# SCH_linefollower_2024-05-15.net
KiCad netlist of a schematic drawn in EasyEDA
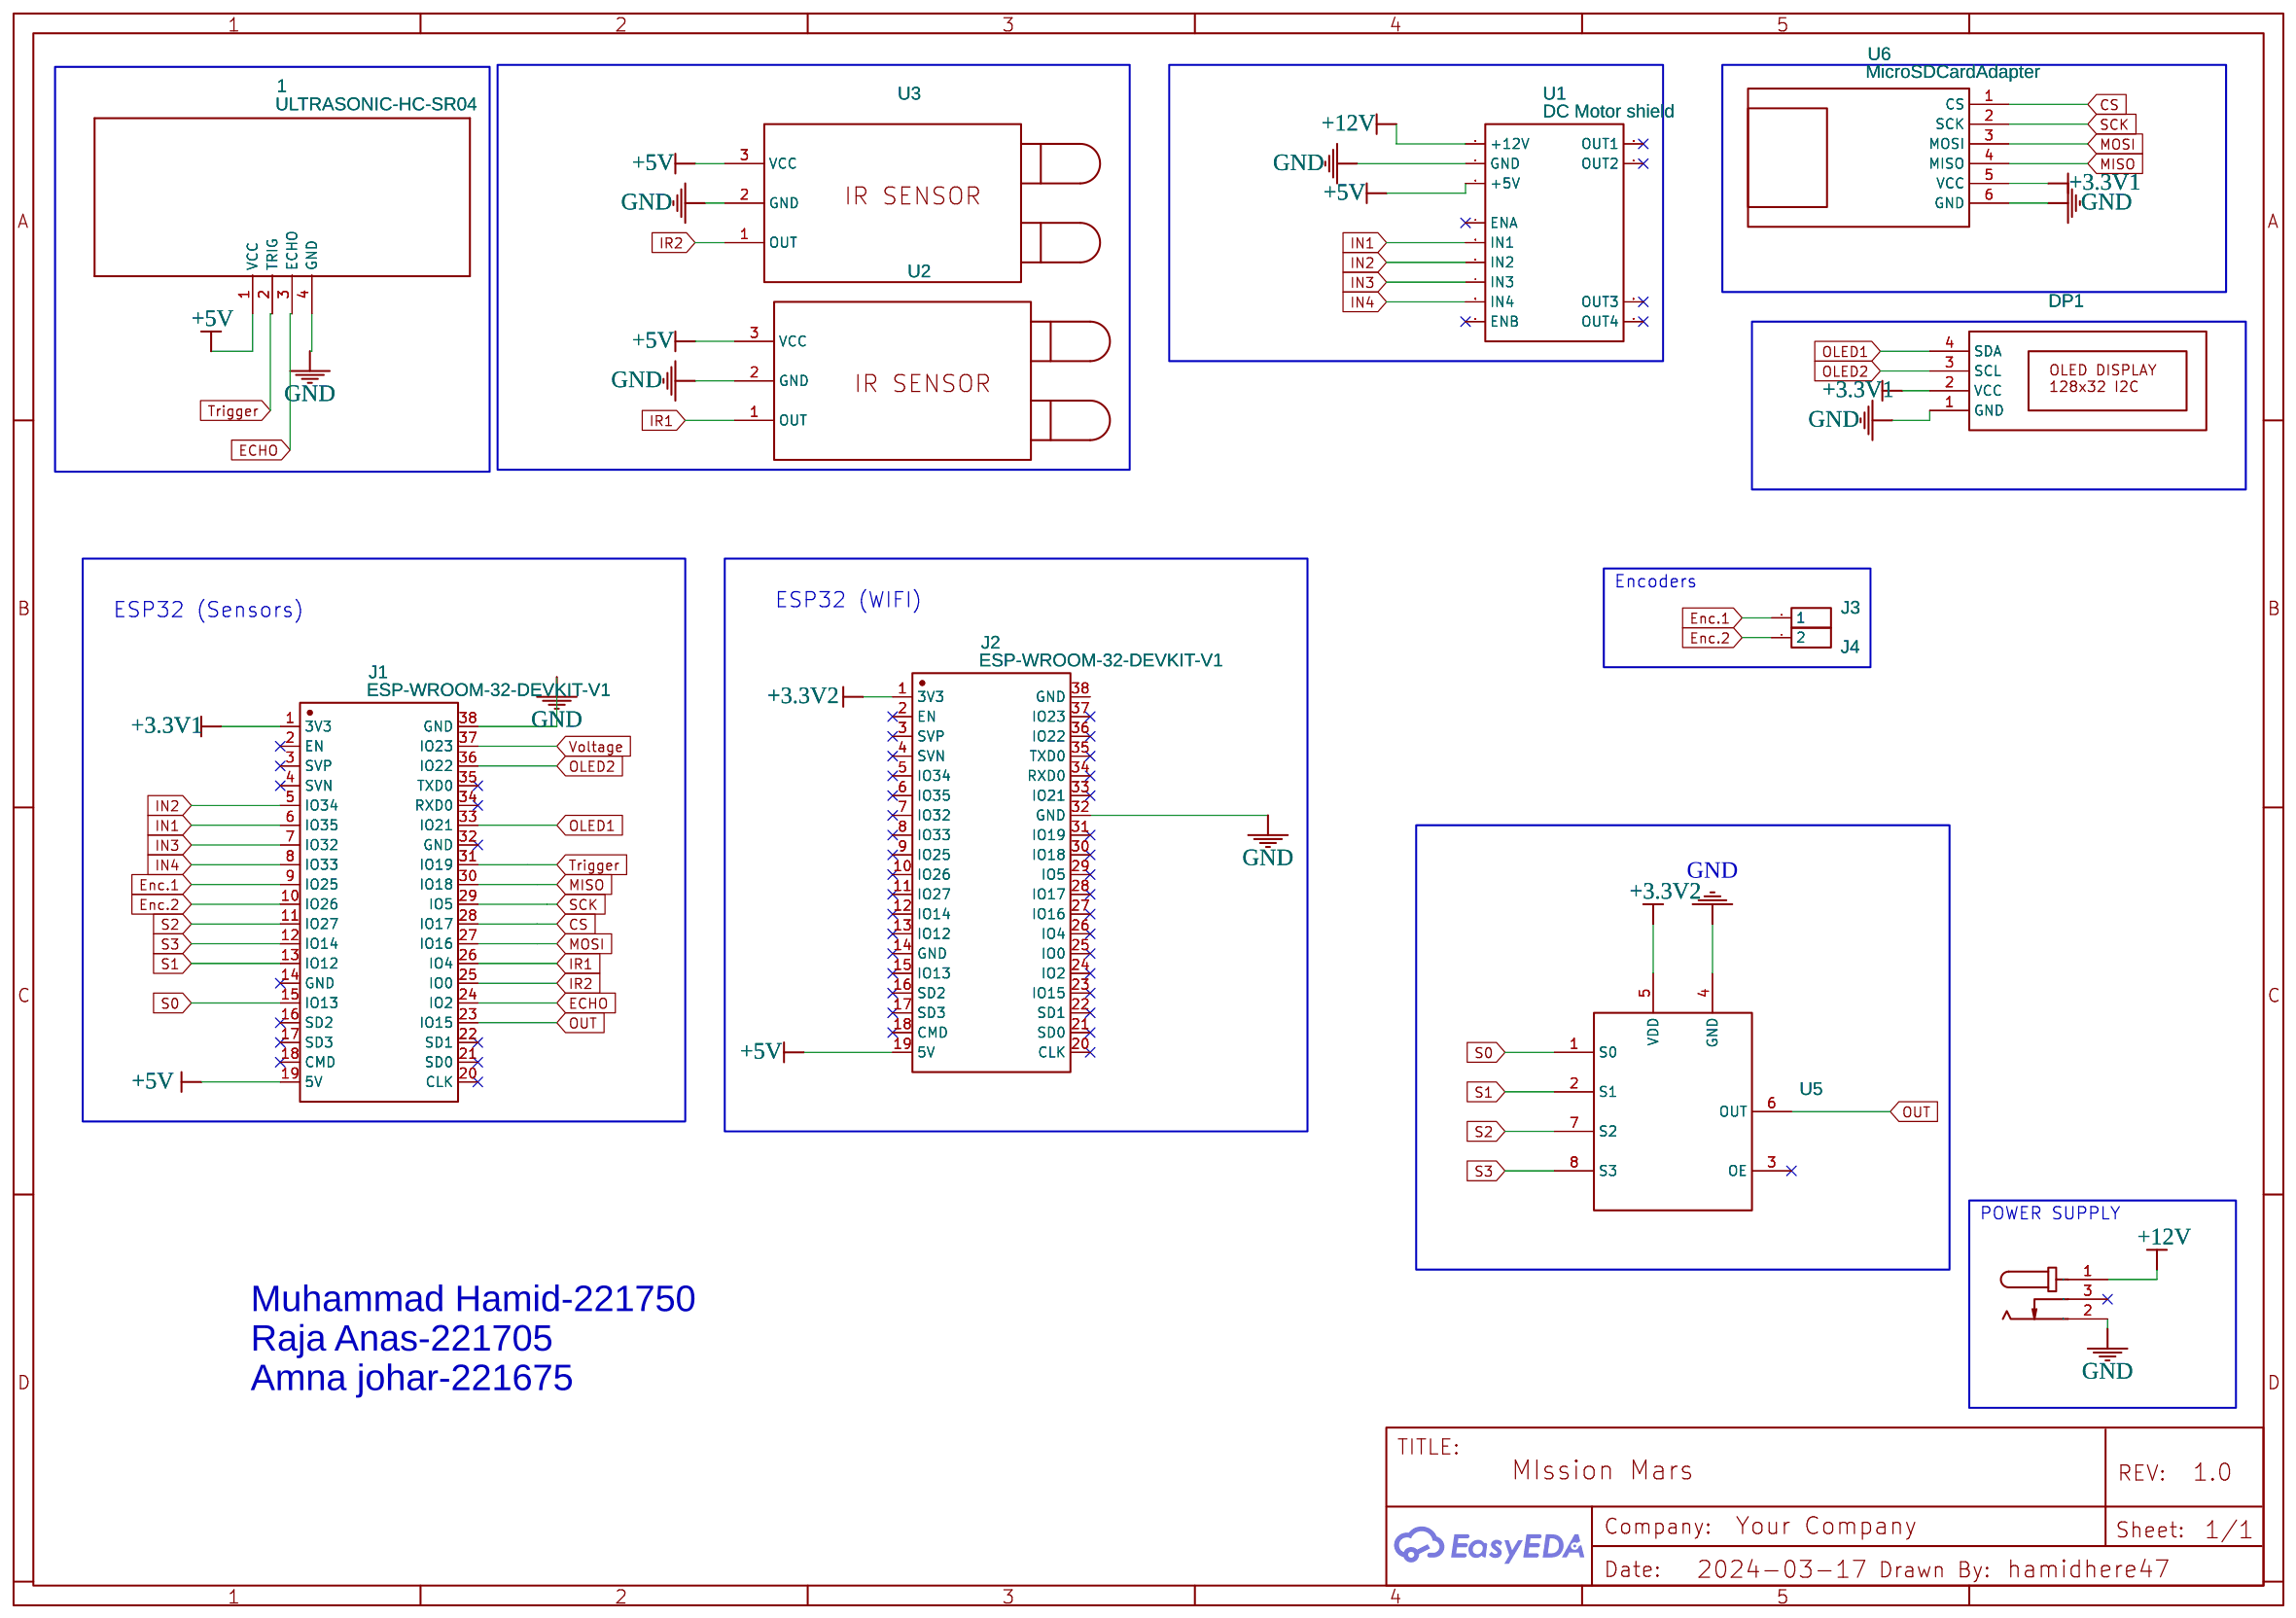
[diagram p0: schematic sheet]

(export (version "E")
  (design (tool "Eeschema 10.0.6"))
  (components
    (comp (ref "1") (value "ULTRASONIC-HC-SR04") (libsource (lib "") (part "ULTRASONIC-HC-SR04")))
    (comp (ref "DC1")
      (value "DC005-2.0MM")
      (fields (field (name "Manufacturer") "SOFNG"))
      (libsource (lib "") (part "DC005-2.0MM"))
    )
    (comp (ref "DP1")
      (value "OLED DISPLAY 128x32 0.91\" I2C SSD1306")
      (libsource (lib "") (part "OLED DISPLAY 128x32 0.91{dblquote} I2C SSD1306"))
    )
    (comp (ref "J1") (value "ESP-WROOM-32-DEVKIT-V1") (libsource (lib "") (part "ESP-WROOM-32-DEVKIT-V1")))
    (comp (ref "J2") (value "ESP-WROOM-32-DEVKIT-V1") (libsource (lib "") (part "ESP-WROOM-32-DEVKIT-V1")))
    (comp (ref "J3") (value "HDR-M-2.54_1x1") (libsource (lib "") (part "HDR-M-2.54_1x1_1")))
    (comp (ref "J4") (value "HDR-M-2.54_1x1") (libsource (lib "") (part "HDR-M-2.54_1x1")))
    (comp (ref "U1") (value "DC Motor shield") (libsource (lib "") (part "DC Motor shield")))
    (comp (ref "U2")
      (value "IR PROXIMITY SENSOR MODULE PSH")
      (libsource (lib "") (part "IR PROXIMITY SENSOR MODULE PSH_1"))
    )
    (comp (ref "U3")
      (value "IR PROXIMITY SENSOR MODULE PSH")
      (libsource (lib "") (part "IR PROXIMITY SENSOR MODULE PSH"))
    )
    (comp (ref "U5")
      (value "TCS3200 _ Symbol Schematic")
      (libsource (lib "") (part "TCS3200 _ Symbol Schematic"))
    )
    (comp (ref "U6") (value "MicroSDCardAdapter") (libsource (lib "") (part "MicroSDCardAdapter")))
  )
  (nets
    (net (code "1") (name "+3.3V1") (class "Default")
      (node (ref "DP1") (pin "2") (pinfunction "VCC_2") (pintype "unspecified"))
      (node (ref "J1") (pin "1") (pinfunction "3V3_1") (pintype "unspecified"))
      (node (ref "U6") (pin "5") (pinfunction "VCC_5") (pintype "unspecified"))
    )
    (net (code "2") (name "+3.3V2") (class "Default")
      (node (ref "J2") (pin "1") (pinfunction "3V3_1") (pintype "unspecified"))
      (node (ref "U5") (pin "5") (pinfunction "VDD_5") (pintype "unspecified"))
    )
    (net (code "3") (name "+5V") (class "Default")
      (node (ref "1") (pin "1") (pinfunction "VCC_1") (pintype "bidirectional"))
      (node (ref "J1") (pin "19") (pinfunction "5V_19") (pintype "unspecified"))
      (node (ref "J2") (pin "19") (pinfunction "5V_19") (pintype "unspecified"))
      (node (ref "U1") (pin "3") (pinfunction "+5V_3") (pintype "unspecified"))
      (node (ref "U2") (pin "3") (pinfunction "VCC_3") (pintype "unspecified"))
      (node (ref "U3") (pin "3") (pinfunction "VCC_3") (pintype "unspecified"))
    )
    (net (code "4") (name "+12V") (class "Default")
      (node (ref "DC1") (pin "1") (pinfunction "1_1") (pintype "unspecified"))
      (node (ref "U1") (pin "1") (pinfunction "+12V_1") (pintype "unspecified"))
    )
    (net (code "5") (name "CS") (class "Default")
      (node (ref "J1") (pin "28") (pinfunction "IO17_28") (pintype "unspecified"))
      (node (ref "U6") (pin "1") (pinfunction "CS_1") (pintype "unspecified"))
    )
    (net (code "6") (name "ECHO") (class "Default")
      (node (ref "1") (pin "3") (pinfunction "ECHO_3") (pintype "bidirectional"))
      (node (ref "J1") (pin "24") (pinfunction "IO2_24") (pintype "unspecified"))
    )
    (net (code "7") (name "Enc.1") (class "Default")
      (node (ref "J1") (pin "9") (pinfunction "IO25_9") (pintype "unspecified"))
      (node (ref "J3") (pin "1") (pinfunction "1_1") (pintype "input"))
    )
    (net (code "8") (name "Enc.2") (class "Default")
      (node (ref "J1") (pin "10") (pinfunction "IO26_10") (pintype "unspecified"))
      (node (ref "J4") (pin "1") (pinfunction "2_1") (pintype "input"))
    )
    (net (code "9") (name "GND") (class "Default")
      (node (ref "1") (pin "4") (pinfunction "GND_4") (pintype "bidirectional"))
      (node (ref "DC1") (pin "2") (pinfunction "2_2") (pintype "unspecified"))
      (node (ref "DP1") (pin "1") (pinfunction "GND_1") (pintype "unspecified"))
      (node (ref "J1") (pin "38") (pinfunction "GND_38") (pintype "unspecified"))
      (node (ref "J2") (pin "32") (pinfunction "GND_32") (pintype "unspecified"))
      (node (ref "U1") (pin "2") (pinfunction "GND_2") (pintype "unspecified"))
      (node (ref "U2") (pin "2") (pinfunction "GND_2") (pintype "unspecified"))
      (node (ref "U3") (pin "2") (pinfunction "GND_2") (pintype "unspecified"))
      (node (ref "U5") (pin "4") (pinfunction "GND_4") (pintype "unspecified"))
      (node (ref "U6") (pin "6") (pinfunction "GND_6") (pintype "unspecified"))
    )
    (net (code "10") (name "IN1") (class "Default")
      (node (ref "J1") (pin "6") (pinfunction "IO35_6") (pintype "unspecified"))
      (node (ref "U1") (pin "5") (pinfunction "IN1_5") (pintype "unspecified"))
    )
    (net (code "11") (name "IN2") (class "Default")
      (node (ref "J1") (pin "5") (pinfunction "IO34_5") (pintype "unspecified"))
      (node (ref "U1") (pin "6") (pinfunction "IN2_6") (pintype "unspecified"))
    )
    (net (code "12") (name "IN3") (class "Default")
      (node (ref "J1") (pin "7") (pinfunction "IO32_7") (pintype "unspecified"))
      (node (ref "U1") (pin "7") (pinfunction "IN3_7") (pintype "unspecified"))
    )
    (net (code "13") (name "IN4") (class "Default")
      (node (ref "J1") (pin "8") (pinfunction "IO33_8") (pintype "unspecified"))
      (node (ref "U1") (pin "8") (pinfunction "IN4_8") (pintype "unspecified"))
    )
    (net (code "14") (name "IR1") (class "Default")
      (node (ref "J1") (pin "26") (pinfunction "IO4_26") (pintype "unspecified"))
      (node (ref "U2") (pin "1") (pinfunction "OUT_1") (pintype "unspecified"))
    )
    (net (code "15") (name "IR2") (class "Default")
      (node (ref "J1") (pin "25") (pinfunction "IO0_25") (pintype "unspecified"))
      (node (ref "U3") (pin "1") (pinfunction "OUT_1") (pintype "unspecified"))
    )
    (net (code "16") (name "MISO") (class "Default")
      (node (ref "J1") (pin "30") (pinfunction "IO18_30") (pintype "unspecified"))
      (node (ref "U6") (pin "4") (pinfunction "MISO_4") (pintype "unspecified"))
    )
    (net (code "17") (name "MOSI") (class "Default")
      (node (ref "J1") (pin "27") (pinfunction "IO16_27") (pintype "unspecified"))
      (node (ref "U6") (pin "3") (pinfunction "MOSI_3") (pintype "unspecified"))
    )
    (net (code "18") (name "OLED1") (class "Default")
      (node (ref "DP1") (pin "4") (pinfunction "SDA_4") (pintype "unspecified"))
      (node (ref "J1") (pin "33") (pinfunction "IO21_33") (pintype "unspecified"))
    )
    (net (code "19") (name "OLED2") (class "Default")
      (node (ref "DP1") (pin "3") (pinfunction "SCL_3") (pintype "unspecified"))
      (node (ref "J1") (pin "36") (pinfunction "IO22_36") (pintype "unspecified"))
    )
    (net (code "20") (name "OUT") (class "Default")
      (node (ref "J1") (pin "23") (pinfunction "IO15_23") (pintype "unspecified"))
      (node (ref "U5") (pin "6") (pinfunction "OUT_6") (pintype "unspecified"))
    )
    (net (code "21") (name "S0") (class "Default")
      (node (ref "J1") (pin "15") (pinfunction "IO13_15") (pintype "unspecified"))
      (node (ref "U5") (pin "1") (pinfunction "S0_1") (pintype "unspecified"))
    )
    (net (code "22") (name "S1") (class "Default")
      (node (ref "J1") (pin "13") (pinfunction "IO12_13") (pintype "unspecified"))
      (node (ref "U5") (pin "2") (pinfunction "S1_2") (pintype "unspecified"))
    )
    (net (code "23") (name "S2") (class "Default")
      (node (ref "J1") (pin "11") (pinfunction "IO27_11") (pintype "unspecified"))
      (node (ref "U5") (pin "7") (pinfunction "S2_7") (pintype "unspecified"))
    )
    (net (code "24") (name "S3") (class "Default")
      (node (ref "J1") (pin "12") (pinfunction "IO14_12") (pintype "unspecified"))
      (node (ref "U5") (pin "8") (pinfunction "S3_8") (pintype "unspecified"))
    )
    (net (code "25") (name "SCK") (class "Default")
      (node (ref "J1") (pin "29") (pinfunction "IO5_29") (pintype "unspecified"))
      (node (ref "U6") (pin "2") (pinfunction "SCK_2") (pintype "unspecified"))
    )
    (net (code "26") (name "Trigger") (class "Default")
      (node (ref "1") (pin "2") (pinfunction "TRIG_2") (pintype "bidirectional"))
      (node (ref "J1") (pin "31") (pinfunction "IO19_31") (pintype "unspecified"))
    )
    (net (code "27") (name "Voltage") (class "Default")
      (node (ref "J1") (pin "37") (pinfunction "IO23_37") (pintype "unspecified"))
    )
    (net (code "28") (name "unconnected-(DC1-Pad3)") (class "Default")
      (node (ref "DC1") (pin "3") (pinfunction "3_3") (pintype "unspecified+no_connect"))
    )
    (net (code "29") (name "unconnected-(J1-CLK-Pad20)") (class "Default")
      (node (ref "J1") (pin "20") (pinfunction "CLK_20") (pintype "unspecified+no_connect"))
    )
    (net (code "30") (name "unconnected-(J1-CMD-Pad18)") (class "Default")
      (node (ref "J1") (pin "18") (pinfunction "CMD_18") (pintype "unspecified+no_connect"))
    )
    (net (code "31") (name "unconnected-(J1-EN-Pad2)") (class "Default")
      (node (ref "J1") (pin "2") (pinfunction "EN_2") (pintype "unspecified+no_connect"))
    )
    (net (code "32") (name "unconnected-(J1-GND-Pad14)") (class "Default")
      (node (ref "J1") (pin "14") (pinfunction "GND_14") (pintype "unspecified+no_connect"))
    )
    (net (code "33") (name "unconnected-(J1-GND-Pad32)") (class "Default")
      (node (ref "J1") (pin "32") (pinfunction "GND_32") (pintype "unspecified+no_connect"))
    )
    (net (code "34") (name "unconnected-(J1-RXD0-Pad34)") (class "Default")
      (node (ref "J1") (pin "34") (pinfunction "RXD0_34") (pintype "unspecified+no_connect"))
    )
    (net (code "35") (name "unconnected-(J1-SD0-Pad21)") (class "Default")
      (node (ref "J1") (pin "21") (pinfunction "SD0_21") (pintype "unspecified+no_connect"))
    )
    (net (code "36") (name "unconnected-(J1-SD1-Pad22)") (class "Default")
      (node (ref "J1") (pin "22") (pinfunction "SD1_22") (pintype "unspecified+no_connect"))
    )
    (net (code "37") (name "unconnected-(J1-SD2-Pad16)") (class "Default")
      (node (ref "J1") (pin "16") (pinfunction "SD2_16") (pintype "unspecified+no_connect"))
    )
    (net (code "38") (name "unconnected-(J1-SD3-Pad17)") (class "Default")
      (node (ref "J1") (pin "17") (pinfunction "SD3_17") (pintype "unspecified+no_connect"))
    )
    (net (code "39") (name "unconnected-(J1-SVN-Pad4)") (class "Default")
      (node (ref "J1") (pin "4") (pinfunction "SVN_4") (pintype "unspecified+no_connect"))
    )
    (net (code "40") (name "unconnected-(J1-SVP-Pad3)") (class "Default")
      (node (ref "J1") (pin "3") (pinfunction "SVP_3") (pintype "unspecified+no_connect"))
    )
    (net (code "41") (name "unconnected-(J1-TXD0-Pad35)") (class "Default")
      (node (ref "J1") (pin "35") (pinfunction "TXD0_35") (pintype "unspecified+no_connect"))
    )
    (net (code "42") (name "unconnected-(J2-CLK-Pad20)") (class "Default")
      (node (ref "J2") (pin "20") (pinfunction "CLK_20") (pintype "unspecified+no_connect"))
    )
    (net (code "43") (name "unconnected-(J2-CMD-Pad18)") (class "Default")
      (node (ref "J2") (pin "18") (pinfunction "CMD_18") (pintype "unspecified+no_connect"))
    )
    (net (code "44") (name "unconnected-(J2-EN-Pad2)") (class "Default")
      (node (ref "J2") (pin "2") (pinfunction "EN_2") (pintype "unspecified+no_connect"))
    )
    (net (code "45") (name "unconnected-(J2-GND-Pad14)") (class "Default")
      (node (ref "J2") (pin "14") (pinfunction "GND_14") (pintype "unspecified+no_connect"))
    )
    (net (code "46") (name "unconnected-(J2-GND-Pad38)") (class "Default")
      (node (ref "J2") (pin "38") (pinfunction "GND_38") (pintype "unspecified"))
    )
    (net (code "47") (name "unconnected-(J2-IO0-Pad25)") (class "Default")
      (node (ref "J2") (pin "25") (pinfunction "IO0_25") (pintype "unspecified+no_connect"))
    )
    (net (code "48") (name "unconnected-(J2-IO2-Pad24)") (class "Default")
      (node (ref "J2") (pin "24") (pinfunction "IO2_24") (pintype "unspecified+no_connect"))
    )
    (net (code "49") (name "unconnected-(J2-IO4-Pad26)") (class "Default")
      (node (ref "J2") (pin "26") (pinfunction "IO4_26") (pintype "unspecified+no_connect"))
    )
    (net (code "50") (name "unconnected-(J2-IO5-Pad29)") (class "Default")
      (node (ref "J2") (pin "29") (pinfunction "IO5_29") (pintype "unspecified+no_connect"))
    )
    (net (code "51") (name "unconnected-(J2-IO12-Pad13)") (class "Default")
      (node (ref "J2") (pin "13") (pinfunction "IO12_13") (pintype "unspecified+no_connect"))
    )
    (net (code "52") (name "unconnected-(J2-IO13-Pad15)") (class "Default")
      (node (ref "J2") (pin "15") (pinfunction "IO13_15") (pintype "unspecified+no_connect"))
    )
    (net (code "53") (name "unconnected-(J2-IO14-Pad12)") (class "Default")
      (node (ref "J2") (pin "12") (pinfunction "IO14_12") (pintype "unspecified+no_connect"))
    )
    (net (code "54") (name "unconnected-(J2-IO15-Pad23)") (class "Default")
      (node (ref "J2") (pin "23") (pinfunction "IO15_23") (pintype "unspecified+no_connect"))
    )
    (net (code "55") (name "unconnected-(J2-IO16-Pad27)") (class "Default")
      (node (ref "J2") (pin "27") (pinfunction "IO16_27") (pintype "unspecified+no_connect"))
    )
    (net (code "56") (name "unconnected-(J2-IO17-Pad28)") (class "Default")
      (node (ref "J2") (pin "28") (pinfunction "IO17_28") (pintype "unspecified+no_connect"))
    )
    (net (code "57") (name "unconnected-(J2-IO18-Pad30)") (class "Default")
      (node (ref "J2") (pin "30") (pinfunction "IO18_30") (pintype "unspecified+no_connect"))
    )
    (net (code "58") (name "unconnected-(J2-IO19-Pad31)") (class "Default")
      (node (ref "J2") (pin "31") (pinfunction "IO19_31") (pintype "unspecified+no_connect"))
    )
    (net (code "59") (name "unconnected-(J2-IO21-Pad33)") (class "Default")
      (node (ref "J2") (pin "33") (pinfunction "IO21_33") (pintype "unspecified+no_connect"))
    )
    (net (code "60") (name "unconnected-(J2-IO22-Pad36)") (class "Default")
      (node (ref "J2") (pin "36") (pinfunction "IO22_36") (pintype "unspecified+no_connect"))
    )
    (net (code "61") (name "unconnected-(J2-IO23-Pad37)") (class "Default")
      (node (ref "J2") (pin "37") (pinfunction "IO23_37") (pintype "unspecified+no_connect"))
    )
    (net (code "62") (name "unconnected-(J2-IO25-Pad9)") (class "Default")
      (node (ref "J2") (pin "9") (pinfunction "IO25_9") (pintype "unspecified+no_connect"))
    )
    (net (code "63") (name "unconnected-(J2-IO26-Pad10)") (class "Default")
      (node (ref "J2") (pin "10") (pinfunction "IO26_10") (pintype "unspecified+no_connect"))
    )
    (net (code "64") (name "unconnected-(J2-IO27-Pad11)") (class "Default")
      (node (ref "J2") (pin "11") (pinfunction "IO27_11") (pintype "unspecified+no_connect"))
    )
    (net (code "65") (name "unconnected-(J2-IO32-Pad7)") (class "Default")
      (node (ref "J2") (pin "7") (pinfunction "IO32_7") (pintype "unspecified+no_connect"))
    )
    (net (code "66") (name "unconnected-(J2-IO33-Pad8)") (class "Default")
      (node (ref "J2") (pin "8") (pinfunction "IO33_8") (pintype "unspecified+no_connect"))
    )
    (net (code "67") (name "unconnected-(J2-IO34-Pad5)") (class "Default")
      (node (ref "J2") (pin "5") (pinfunction "IO34_5") (pintype "unspecified+no_connect"))
    )
    (net (code "68") (name "unconnected-(J2-IO35-Pad6)") (class "Default")
      (node (ref "J2") (pin "6") (pinfunction "IO35_6") (pintype "unspecified+no_connect"))
    )
    (net (code "69") (name "unconnected-(J2-RXD0-Pad34)") (class "Default")
      (node (ref "J2") (pin "34") (pinfunction "RXD0_34") (pintype "unspecified+no_connect"))
    )
    (net (code "70") (name "unconnected-(J2-SD0-Pad21)") (class "Default")
      (node (ref "J2") (pin "21") (pinfunction "SD0_21") (pintype "unspecified+no_connect"))
    )
    (net (code "71") (name "unconnected-(J2-SD1-Pad22)") (class "Default")
      (node (ref "J2") (pin "22") (pinfunction "SD1_22") (pintype "unspecified+no_connect"))
    )
    (net (code "72") (name "unconnected-(J2-SD2-Pad16)") (class "Default")
      (node (ref "J2") (pin "16") (pinfunction "SD2_16") (pintype "unspecified+no_connect"))
    )
    (net (code "73") (name "unconnected-(J2-SD3-Pad17)") (class "Default")
      (node (ref "J2") (pin "17") (pinfunction "SD3_17") (pintype "unspecified+no_connect"))
    )
    (net (code "74") (name "unconnected-(J2-SVN-Pad4)") (class "Default")
      (node (ref "J2") (pin "4") (pinfunction "SVN_4") (pintype "unspecified+no_connect"))
    )
    (net (code "75") (name "unconnected-(J2-SVP-Pad3)") (class "Default")
      (node (ref "J2") (pin "3") (pinfunction "SVP_3") (pintype "unspecified+no_connect"))
    )
    (net (code "76") (name "unconnected-(J2-TXD0-Pad35)") (class "Default")
      (node (ref "J2") (pin "35") (pinfunction "TXD0_35") (pintype "unspecified+no_connect"))
    )
    (net (code "77") (name "unconnected-(U1-ENA-Pad4)") (class "Default")
      (node (ref "U1") (pin "4") (pinfunction "ENA_4") (pintype "unspecified+no_connect"))
    )
    (net (code "78") (name "unconnected-(U1-ENB-Pad9)") (class "Default")
      (node (ref "U1") (pin "9") (pinfunction "ENB_9") (pintype "unspecified+no_connect"))
    )
    (net (code "79") (name "unconnected-(U1-OUT1-Pad10)") (class "Default")
      (node (ref "U1") (pin "10") (pinfunction "OUT1_10") (pintype "unspecified+no_connect"))
    )
    (net (code "80") (name "unconnected-(U1-OUT2-Pad11)") (class "Default")
      (node (ref "U1") (pin "11") (pinfunction "OUT2_11") (pintype "unspecified+no_connect"))
    )
    (net (code "81") (name "unconnected-(U1-OUT3-Pad13)") (class "Default")
      (node (ref "U1") (pin "13") (pinfunction "OUT3_13") (pintype "unspecified+no_connect"))
    )
    (net (code "82") (name "unconnected-(U1-OUT4-Pad12)") (class "Default")
      (node (ref "U1") (pin "12") (pinfunction "OUT4_12") (pintype "unspecified+no_connect"))
    )
    (net (code "83") (name "unconnected-(U5-OE-Pad3)") (class "Default")
      (node (ref "U5") (pin "3") (pinfunction "OE_3") (pintype "unspecified+no_connect"))
    )
  )
)
